# smarty02.net
KiCad netlist of a schematic drawn in EAGLE
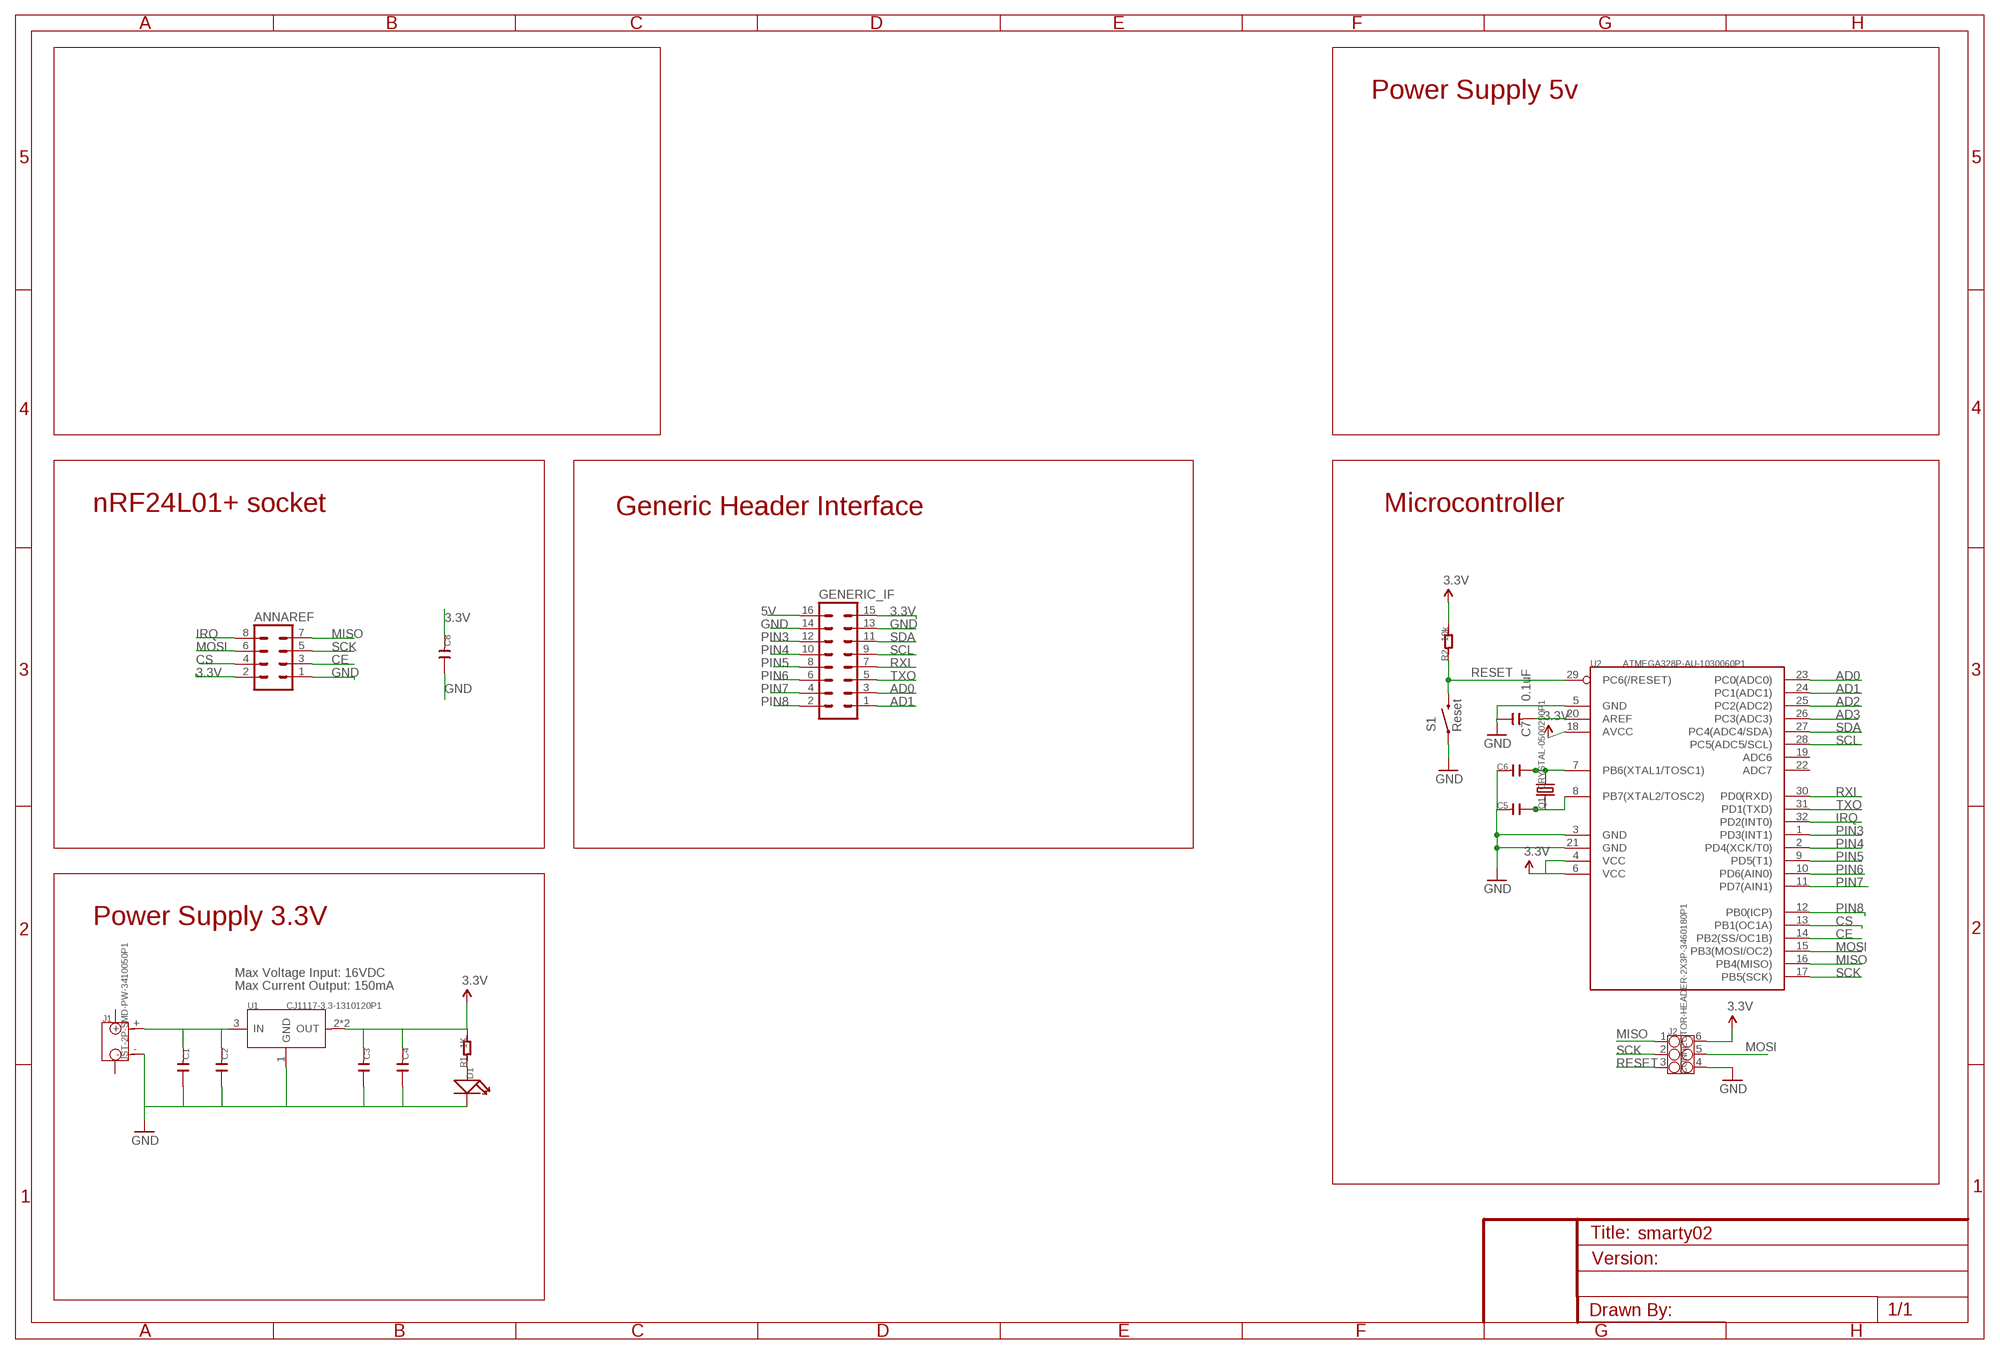
[diagram p0: schematic, sheet 1]

(export (version "E")
  (design (tool "Eeschema 10.0.6"))
  (components
    (comp (ref "ANNAREF")
      (value "MA04-2")
      (footprint "eagle-import:MA04-2")
      (libsource (lib "eagle-import") (part "MA04-2"))
    )
    (comp (ref "C1")
      (value "C-0603")
      (footprint "eagle-import:C0603")
      (libsource (lib "eagle-import") (part "C-0603"))
    )
    (comp (ref "C2")
      (value "C-0805")
      (footprint "eagle-import:C0805")
      (libsource (lib "eagle-import") (part "C-0805"))
    )
    (comp (ref "C3")
      (value "C-0603")
      (footprint "eagle-import:C0603")
      (libsource (lib "eagle-import") (part "C-0603"))
    )
    (comp (ref "C4")
      (value "C-0805")
      (footprint "eagle-import:C0805")
      (libsource (lib "eagle-import") (part "C-0805"))
    )
    (comp (ref "C5")
      (value "C-0603")
      (footprint "eagle-import:C0603")
      (libsource (lib "eagle-import") (part "C-0603"))
    )
    (comp (ref "C6")
      (value "C-0603")
      (footprint "eagle-import:C0603")
      (libsource (lib "eagle-import") (part "C-0603"))
    )
    (comp (ref "C7")
      (value "0.1uF")
      (footprint "eagle-import:C0805")
      (libsource (lib "eagle-import") (part "C-0805"))
    )
    (comp (ref "C8")
      (value "C-0805")
      (footprint "eagle-import:C0805")
      (libsource (lib "eagle-import") (part "C-0805"))
    )
    (comp (ref "D1")
      (value "LED")
      (footprint "eagle-import:LED0603")
      (libsource (lib "eagle-import") (part "LED"))
    )
    (comp (ref "GENERIC_IF")
      (value "MA08-2")
      (footprint "eagle-import:MA08-2")
      (libsource (lib "eagle-import") (part "MA08-2"))
    )
    (comp (ref "J1")
      (value "JST-2P-SMD-PW-3410050P1")
      (footprint "eagle-import:2P-SMD-2.0-90D")
      (libsource (lib "eagle-import") (part "JST-2P-SMD-PW-3410050P1"))
    )
    (comp (ref "J2")
      (value "CONNECTOR-HEADER-2X3P-3460180P1")
      (footprint "eagle-import:2X3P-2.54-2.54-11.6-3.0-BLACK-MALE")
      (libsource (lib "eagle-import") (part "CONNECTOR-HEADER-2X3P-3460180P1"))
    )
    (comp (ref "Q1")
      (value "CRYSTAL-0500290P1")
      (footprint "eagle-import:2P-SMD-5.0X3.2")
      (libsource (lib "eagle-import") (part "CRYSTAL-0500290P1"))
    )
    (comp (ref "R1")
      (value "1K")
      (footprint "eagle-import:R0603")
      (libsource (lib "eagle-import") (part "R-0603"))
    )
    (comp (ref "R2")
      (value "10k")
      (footprint "eagle-import:R0603")
      (libsource (lib "eagle-import") (part "R-0603"))
    )
    (comp (ref "S1")
      (value "Reset")
      (footprint "eagle-import:TACTILE_SWITCH_SMD")
      (libsource (lib "eagle-import") (part "SWITCH-MOMENTARY-2SMD"))
    )
    (comp (ref "U1")
      (value "CJ1117-3.3-1310120P1")
      (footprint "eagle-import:SOT89")
      (libsource (lib "eagle-import") (part "CJ1117-3.3-1310120P1"))
    )
    (comp (ref "U2")
      (value "ATMEGA328P-AU-1030060P1")
      (footprint "eagle-import:TQFP32")
      (libsource (lib "eagle-import") (part "ATMEGA328P-AU-1030060P1"))
    )
  )
  (nets
    (net (code "1") (name "/5V") (class "Default")
      (node (ref "GENERIC_IF") (pin "16") (pinfunction "16_16") (pintype "passive"))
    )
    (net (code "2") (name "/AD0") (class "Default")
      (node (ref "GENERIC_IF") (pin "3") (pinfunction "3_3") (pintype "passive"))
      (node (ref "U2") (pin "23") (pinfunction "PC0(ADC0)_23") (pintype "bidirectional"))
    )
    (net (code "3") (name "/AD1") (class "Default")
      (node (ref "GENERIC_IF") (pin "1") (pinfunction "1_1") (pintype "passive"))
      (node (ref "U2") (pin "24") (pinfunction "PC1(ADC1)_24") (pintype "bidirectional"))
    )
    (net (code "4") (name "/AD2") (class "Default")
      (node (ref "U2") (pin "25") (pinfunction "PC2(ADC2)_25") (pintype "bidirectional"))
    )
    (net (code "5") (name "/AD3") (class "Default")
      (node (ref "U2") (pin "26") (pinfunction "PC3(ADC3)_26") (pintype "bidirectional"))
    )
    (net (code "6") (name "/CE") (class "Default")
      (node (ref "ANNAREF") (pin "3") (pinfunction "3_3") (pintype "passive"))
      (node (ref "U2") (pin "14") (pinfunction "PB2(SS/OC1B)_14") (pintype "bidirectional"))
    )
    (net (code "7") (name "/CS") (class "Default")
      (node (ref "ANNAREF") (pin "4") (pinfunction "4_4") (pintype "passive"))
      (node (ref "U2") (pin "13") (pinfunction "PB1(OC1A)_13") (pintype "bidirectional"))
    )
    (net (code "8") (name "/IRQ") (class "Default")
      (node (ref "ANNAREF") (pin "8") (pinfunction "8_8") (pintype "passive"))
      (node (ref "U2") (pin "32") (pinfunction "PD2(INT0)_32") (pintype "bidirectional"))
    )
    (net (code "9") (name "/MISO") (class "Default")
      (node (ref "ANNAREF") (pin "7") (pinfunction "7_7") (pintype "passive"))
      (node (ref "J2") (pin "1") (pinfunction "1_1") (pintype "bidirectional"))
      (node (ref "U2") (pin "16") (pinfunction "PB4(MISO)_16") (pintype "bidirectional"))
    )
    (net (code "10") (name "/MOSI") (class "Default")
      (node (ref "ANNAREF") (pin "6") (pinfunction "6_6") (pintype "passive"))
      (node (ref "J2") (pin "5") (pinfunction "5_5") (pintype "bidirectional"))
      (node (ref "U2") (pin "15") (pinfunction "PB3(MOSI/OC2)_15") (pintype "bidirectional"))
    )
    (net (code "11") (name "/PIN3") (class "Default")
      (node (ref "GENERIC_IF") (pin "12") (pinfunction "12_12") (pintype "passive"))
      (node (ref "U2") (pin "1") (pinfunction "PD3(INT1)_1") (pintype "bidirectional"))
    )
    (net (code "12") (name "/PIN4") (class "Default")
      (node (ref "GENERIC_IF") (pin "10") (pinfunction "10_10") (pintype "passive"))
      (node (ref "U2") (pin "2") (pinfunction "PD4(XCK/T0)_2") (pintype "bidirectional"))
    )
    (net (code "13") (name "/PIN5") (class "Default")
      (node (ref "GENERIC_IF") (pin "8") (pinfunction "8_8") (pintype "passive"))
      (node (ref "U2") (pin "9") (pinfunction "PD5(T1)_9") (pintype "bidirectional"))
    )
    (net (code "14") (name "/PIN6") (class "Default")
      (node (ref "GENERIC_IF") (pin "6") (pinfunction "6_6") (pintype "passive"))
      (node (ref "U2") (pin "10") (pinfunction "PD6(AIN0)_10") (pintype "bidirectional"))
    )
    (net (code "15") (name "/PIN7") (class "Default")
      (node (ref "GENERIC_IF") (pin "4") (pinfunction "4_4") (pintype "passive"))
      (node (ref "U2") (pin "11") (pinfunction "PD7(AIN1)_11") (pintype "bidirectional"))
    )
    (net (code "16") (name "/PIN8") (class "Default")
      (node (ref "GENERIC_IF") (pin "2") (pinfunction "2_2") (pintype "passive"))
      (node (ref "U2") (pin "12") (pinfunction "PB0(ICP)_12") (pintype "bidirectional"))
    )
    (net (code "17") (name "/RESET") (class "Default")
      (node (ref "J2") (pin "3") (pinfunction "3_3") (pintype "bidirectional"))
      (node (ref "R2") (pin "1") (pinfunction "1_1") (pintype "bidirectional"))
      (node (ref "S1") (pin "3") (pinfunction "2_3") (pintype "passive"))
      (node (ref "U2") (pin "29") (pinfunction "PC6(/RESET)_29") (pintype "bidirectional"))
    )
    (net (code "18") (name "/RXI") (class "Default")
      (node (ref "GENERIC_IF") (pin "7") (pinfunction "7_7") (pintype "passive"))
      (node (ref "U2") (pin "30") (pinfunction "PD0(RXD)_30") (pintype "bidirectional"))
    )
    (net (code "19") (name "/SCK") (class "Default")
      (node (ref "ANNAREF") (pin "5") (pinfunction "5_5") (pintype "passive"))
      (node (ref "J2") (pin "2") (pinfunction "2_2") (pintype "bidirectional"))
      (node (ref "U2") (pin "17") (pinfunction "PB5(SCK)_17") (pintype "bidirectional"))
    )
    (net (code "20") (name "/SCL") (class "Default")
      (node (ref "GENERIC_IF") (pin "9") (pinfunction "9_9") (pintype "passive"))
      (node (ref "U2") (pin "28") (pinfunction "PC5(ADC5/SCL)_28") (pintype "bidirectional"))
    )
    (net (code "21") (name "/SDA") (class "Default")
      (node (ref "GENERIC_IF") (pin "11") (pinfunction "11_11") (pintype "passive"))
      (node (ref "U2") (pin "27") (pinfunction "PC4(ADC4/SDA)_27") (pintype "bidirectional"))
    )
    (net (code "22") (name "/TXO") (class "Default")
      (node (ref "GENERIC_IF") (pin "5") (pinfunction "5_5") (pintype "passive"))
      (node (ref "U2") (pin "31") (pinfunction "PD1(TXD)_31") (pintype "bidirectional"))
    )
    (net (code "23") (name "3.3V") (class "Default")
      (node (ref "ANNAREF") (pin "2") (pinfunction "2_2") (pintype "passive"))
      (node (ref "C3") (pin "1") (pinfunction "1_1") (pintype "bidirectional"))
      (node (ref "C4") (pin "1") (pinfunction "1_1") (pintype "bidirectional"))
      (node (ref "C8") (pin "1") (pinfunction "1_1") (pintype "bidirectional"))
      (node (ref "GENERIC_IF") (pin "15") (pinfunction "15_15") (pintype "passive"))
      (node (ref "J2") (pin "6") (pinfunction "6_6") (pintype "bidirectional"))
      (node (ref "R1") (pin "2") (pinfunction "2_2") (pintype "bidirectional"))
      (node (ref "R2") (pin "2") (pinfunction "2_2") (pintype "bidirectional"))
      (node (ref "U1") (pin "2") (pinfunction "OUT_2") (pintype "bidirectional"))
      (node (ref "U1") (pin "4") (pinfunction "OUT_4") (pintype "bidirectional"))
      (node (ref "U2") (pin "18") (pinfunction "AVCC_18") (pintype "bidirectional"))
      (node (ref "U2") (pin "4") (pinfunction "VCC_4") (pintype "bidirectional"))
      (node (ref "U2") (pin "6") (pinfunction "VCC_6") (pintype "bidirectional"))
    )
    (net (code "24") (name "GND") (class "Default")
      (node (ref "ANNAREF") (pin "1") (pinfunction "1_1") (pintype "passive"))
      (node (ref "C1") (pin "2") (pinfunction "2_2") (pintype "bidirectional"))
      (node (ref "C2") (pin "2") (pinfunction "2_2") (pintype "bidirectional"))
      (node (ref "C3") (pin "2") (pinfunction "2_2") (pintype "bidirectional"))
      (node (ref "C4") (pin "2") (pinfunction "2_2") (pintype "bidirectional"))
      (node (ref "C5") (pin "1") (pinfunction "1_1") (pintype "bidirectional"))
      (node (ref "C6") (pin "1") (pinfunction "1_1") (pintype "bidirectional"))
      (node (ref "C7") (pin "2") (pinfunction "2_2") (pintype "bidirectional"))
      (node (ref "C8") (pin "2") (pinfunction "2_2") (pintype "bidirectional"))
      (node (ref "D1") (pin "-") (pinfunction "-_-") (pintype "passive"))
      (node (ref "GENERIC_IF") (pin "13") (pinfunction "13_13") (pintype "passive"))
      (node (ref "GENERIC_IF") (pin "14") (pinfunction "14_14") (pintype "passive"))
      (node (ref "J1") (pin "-") (pinfunction "-_-") (pintype "bidirectional"))
      (node (ref "J2") (pin "4") (pinfunction "4_4") (pintype "bidirectional"))
      (node (ref "S1") (pin "1") (pinfunction "1_1") (pintype "passive"))
      (node (ref "U1") (pin "1") (pinfunction "GND_1") (pintype "bidirectional"))
      (node (ref "U2") (pin "21") (pinfunction "GND_21") (pintype "bidirectional"))
      (node (ref "U2") (pin "3") (pinfunction "GND_3") (pintype "bidirectional"))
      (node (ref "U2") (pin "5") (pinfunction "GND_5") (pintype "bidirectional"))
    )
    (net (code "25") (name "Net-(D1-Pad+)") (class "Default")
      (node (ref "D1") (pin "+") (pinfunction "+_+") (pintype "passive"))
      (node (ref "R1") (pin "1") (pinfunction "1_1") (pintype "bidirectional"))
    )
    (net (code "26") (name "Net-(U1-IN)") (class "Default")
      (node (ref "C1") (pin "1") (pinfunction "1_1") (pintype "bidirectional"))
      (node (ref "C2") (pin "1") (pinfunction "1_1") (pintype "bidirectional"))
      (node (ref "J1") (pin "+") (pinfunction "+_+") (pintype "bidirectional"))
      (node (ref "U1") (pin "3") (pinfunction "IN_3") (pintype "bidirectional"))
    )
    (net (code "27") (name "Net-(U2-AREF)") (class "Default")
      (node (ref "C7") (pin "1") (pinfunction "1_1") (pintype "bidirectional"))
      (node (ref "U2") (pin "20") (pinfunction "AREF_20") (pintype "bidirectional"))
    )
    (net (code "28") (name "Net-(U2-PB6(XTAL1{slash}TOSC1))") (class "Default")
      (node (ref "C6") (pin "2") (pinfunction "2_2") (pintype "bidirectional"))
      (node (ref "Q1") (pin "2") (pinfunction "2_2") (pintype "passive"))
      (node (ref "U2") (pin "7") (pinfunction "PB6(XTAL1/TOSC1)_7") (pintype "bidirectional"))
    )
    (net (code "29") (name "Net-(U2-PB7(XTAL2{slash}TOSC2))") (class "Default")
      (node (ref "C5") (pin "2") (pinfunction "2_2") (pintype "bidirectional"))
      (node (ref "Q1") (pin "1") (pinfunction "1_1") (pintype "passive"))
      (node (ref "U2") (pin "8") (pinfunction "PB7(XTAL2/TOSC2)_8") (pintype "bidirectional"))
    )
    (net (code "30") (name "unconnected-(J1-Pad3)") (class "Default")
      (node (ref "J1") (pin "3") (pinfunction "3_3") (pintype "bidirectional"))
    )
    (net (code "31") (name "unconnected-(J1-Pad4)") (class "Default")
      (node (ref "J1") (pin "4") (pinfunction "4_4") (pintype "bidirectional"))
    )
    (net (code "32") (name "unconnected-(U2-ADC6-Pad19)") (class "Default")
      (node (ref "U2") (pin "19") (pinfunction "ADC6_19") (pintype "bidirectional"))
    )
    (net (code "33") (name "unconnected-(U2-ADC7-Pad22)") (class "Default")
      (node (ref "U2") (pin "22") (pinfunction "ADC7_22") (pintype "bidirectional"))
    )
  )
)
